# adc.net
KiCad netlist of a schematic drawn in EAGLE
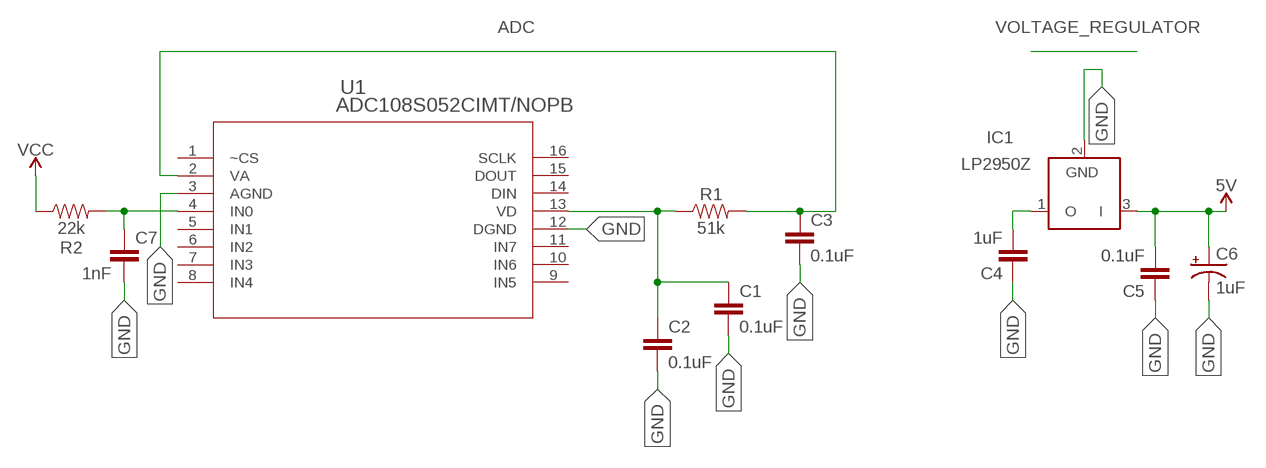
[diagram p0: schematic, sheet 1]

(export (version "E")
  (design (tool "Eeschema 10.0.6"))
  (components
    (comp (ref "C1")
      (value "0.1uF")
      (footprint "eagle-import:0603")
      (libsource (lib "eagle-import") (part "CAP-0603"))
    )
    (comp (ref "C2")
      (value "0.1uF")
      (footprint "eagle-import:0603")
      (libsource (lib "eagle-import") (part "CAP-0603"))
    )
    (comp (ref "C3")
      (value "0.1uF")
      (footprint "eagle-import:0603")
      (libsource (lib "eagle-import") (part "CAP-0603"))
    )
    (comp (ref "C4")
      (value "1uF")
      (footprint "eagle-import:0603")
      (libsource (lib "eagle-import") (part "CAP-0603"))
    )
    (comp (ref "C5")
      (value "0.1uF")
      (footprint "eagle-import:0603")
      (libsource (lib "eagle-import") (part "CAP-0603"))
    )
    (comp (ref "C6")
      (value "1uF")
      (footprint "eagle-import:0603-POLAR")
      (libsource (lib "eagle-import") (part "10UF-POLAR-0603-6.3V-20%(TANT)"))
    )
    (comp (ref "C7")
      (value "1nF")
      (footprint "eagle-import:0603")
      (libsource (lib "eagle-import") (part "CAP-0603"))
    )
    (comp (ref "IC1")
      (value "LP2950Z")
      (footprint "eagle-import:TO92")
      (libsource (lib "eagle-import") (part "LP2950Z"))
    )
    (comp (ref "R1")
      (value "51k")
      (footprint "eagle-import:0603")
      (libsource (lib "eagle-import") (part "RESISTOR0603"))
    )
    (comp (ref "R2")
      (value "22k")
      (footprint "eagle-import:0603")
      (libsource (lib "eagle-import") (part "RESISTOR0603"))
    )
    (comp (ref "U1")
      (value "ADC108S052CIMT/NOPB")
      (footprint "eagle-import:MTC16")
      (fields (field (name "COPYRIGHT") "Copyright (C) 2022 Ultra Librarian. All rights reserved."))
      (libsource (lib "eagle-import") (part "ADC108S052CIMT/NOPB"))
    )
  )
  (nets
    (net (code "1") (name "/ADC") (class "Default")
      (node (ref "C3") (pin "1") (pinfunction "1_1") (pintype "passive"))
      (node (ref "R1") (pin "2") (pinfunction "2_2") (pintype "passive"))
      (node (ref "U1") (pin "2") (pinfunction "VA_2") (pintype "passive"))
    )
    (net (code "3") (name "5V") (class "Default")
      (node (ref "C5") (pin "2") (pinfunction "2_2") (pintype "passive"))
      (node (ref "C6") (pin "+") (pinfunction "+_+") (pintype "passive"))
      (node (ref "IC1") (pin "3") (pinfunction "I_3") (pintype "input"))
    )
    (net (code "4") (name "GND") (class "Default")
      (node (ref "C1") (pin "2") (pinfunction "2_2") (pintype "passive"))
      (node (ref "C2") (pin "2") (pinfunction "2_2") (pintype "passive"))
      (node (ref "C3") (pin "2") (pinfunction "2_2") (pintype "passive"))
      (node (ref "C4") (pin "1") (pinfunction "1_1") (pintype "passive"))
      (node (ref "C5") (pin "1") (pinfunction "1_1") (pintype "passive"))
      (node (ref "C6") (pin "-") (pinfunction "-_-") (pintype "passive"))
      (node (ref "C7") (pin "2") (pinfunction "2_2") (pintype "passive"))
      (node (ref "IC1") (pin "2") (pinfunction "GND_2") (pintype "power_in"))
      (node (ref "U1") (pin "12") (pinfunction "DGND_12") (pintype "passive"))
      (node (ref "U1") (pin "3") (pinfunction "AGND_3") (pintype "passive"))
    )
    (net (code "5") (name "Net-(IC1-O)") (class "Default")
      (node (ref "C4") (pin "2") (pinfunction "2_2") (pintype "passive"))
      (node (ref "IC1") (pin "1") (pinfunction "O_1") (pintype "input"))
    )
    (net (code "6") (name "Net-(U1-IN0)") (class "Default")
      (node (ref "C7") (pin "1") (pinfunction "1_1") (pintype "passive"))
      (node (ref "R2") (pin "2") (pinfunction "2_2") (pintype "passive"))
      (node (ref "U1") (pin "4") (pinfunction "IN0_4") (pintype "input"))
    )
    (net (code "7") (name "Net-(U1-VD)") (class "Default")
      (node (ref "C1") (pin "1") (pinfunction "1_1") (pintype "passive"))
      (node (ref "C2") (pin "1") (pinfunction "1_1") (pintype "passive"))
      (node (ref "R1") (pin "1") (pinfunction "1_1") (pintype "passive"))
      (node (ref "U1") (pin "13") (pinfunction "VD_13") (pintype "passive"))
    )
    (net (code "8") (name "VCC") (class "Default")
      (node (ref "R2") (pin "1") (pinfunction "1_1") (pintype "passive"))
    )
    (net (code "9") (name "unconnected-(U1-DIN-Pad14)") (class "Default")
      (node (ref "U1") (pin "14") (pinfunction "DIN_14") (pintype "input"))
    )
    (net (code "10") (name "unconnected-(U1-DOUT-Pad15)") (class "Default")
      (node (ref "U1") (pin "15") (pinfunction "DOUT_15") (pintype "output"))
    )
    (net (code "11") (name "unconnected-(U1-IN1-Pad5)") (class "Default")
      (node (ref "U1") (pin "5") (pinfunction "IN1_5") (pintype "input"))
    )
    (net (code "12") (name "unconnected-(U1-IN2-Pad6)") (class "Default")
      (node (ref "U1") (pin "6") (pinfunction "IN2_6") (pintype "input"))
    )
    (net (code "13") (name "unconnected-(U1-IN3-Pad7)") (class "Default")
      (node (ref "U1") (pin "7") (pinfunction "IN3_7") (pintype "input"))
    )
    (net (code "14") (name "unconnected-(U1-IN4-Pad8)") (class "Default")
      (node (ref "U1") (pin "8") (pinfunction "IN4_8") (pintype "input"))
    )
    (net (code "15") (name "unconnected-(U1-IN5-Pad9)") (class "Default")
      (node (ref "U1") (pin "9") (pinfunction "IN5_9") (pintype "input"))
    )
    (net (code "16") (name "unconnected-(U1-IN6-Pad10)") (class "Default")
      (node (ref "U1") (pin "10") (pinfunction "IN6_10") (pintype "input"))
    )
    (net (code "17") (name "unconnected-(U1-IN7-Pad11)") (class "Default")
      (node (ref "U1") (pin "11") (pinfunction "IN7_11") (pintype "input"))
    )
    (net (code "18") (name "unconnected-(U1-SCLK-Pad16)") (class "Default")
      (node (ref "U1") (pin "16") (pinfunction "SCLK_16") (pintype "passive"))
    )
    (net (code "19") (name "unconnected-(U1-~{CS}-Pad1)") (class "Default")
      (node (ref "U1") (pin "1") (pinfunction "~{CS}_1") (pintype "passive"))
    )
  )
)
